# 12V_-5V_v_2.net
KiCad netlist of a schematic drawn in EAGLE
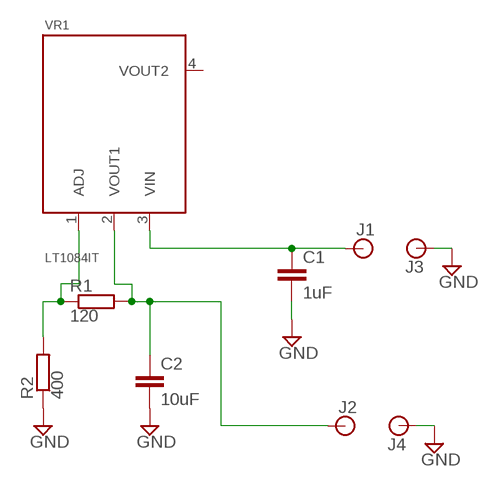
[diagram p0: schematic, sheet 1]

(export (version "E")
  (design (tool "Eeschema 10.0.6"))
  (components
    (comp (ref "C1")
      (value "1uF")
      (footprint "eagle-import:C0805")
      (libsource (lib "eagle-import") (part "C-EUC0805"))
    )
    (comp (ref "C2")
      (value "10uF")
      (footprint "eagle-import:C0805")
      (libsource (lib "eagle-import") (part "C-EUC0805"))
    )
    (comp (ref "J1")
      (value "BANANA_CONN")
      (footprint "eagle-import:BANANA_CONN")
      (libsource (lib "eagle-import") (part "BANANA_CONN"))
    )
    (comp (ref "J2")
      (value "BANANA_CONN")
      (footprint "eagle-import:BANANA_CONN")
      (libsource (lib "eagle-import") (part "BANANA_CONN"))
    )
    (comp (ref "J3")
      (value "BANANA_CONN")
      (footprint "eagle-import:BANANA_CONN")
      (libsource (lib "eagle-import") (part "BANANA_CONN"))
    )
    (comp (ref "J4")
      (value "BANANA_CONN")
      (footprint "eagle-import:BANANA_CONN")
      (libsource (lib "eagle-import") (part "BANANA_CONN"))
    )
    (comp (ref "R1")
      (value "120")
      (footprint "eagle-import:R0805")
      (libsource (lib "eagle-import") (part "R-EU_R0805"))
    )
    (comp (ref "R2")
      (value "400")
      (footprint "eagle-import:R0805")
      (libsource (lib "eagle-import") (part "R-EU_R0805"))
    )
    (comp (ref "VR1")
      (value "LT1084IT")
      (footprint "eagle-import:LT1084IT")
      (fields (field (name "MF") "Linear Technology"))
      (libsource (lib "eagle-import") (part "LT1084IT"))
    )
  )
  (nets
    (net (code "1") (name "GND") (class "Default")
      (node (ref "C1") (pin "2") (pinfunction "2_2") (pintype "passive"))
      (node (ref "C2") (pin "2") (pinfunction "2_2") (pintype "passive"))
      (node (ref "J3") (pin "P$1") (pinfunction "1_P$1") (pintype "passive"))
      (node (ref "J4") (pin "P$1") (pinfunction "1_P$1") (pintype "passive"))
      (node (ref "R2") (pin "1") (pinfunction "1_1") (pintype "passive"))
    )
    (net (code "2") (name "Net-(J1-1)") (class "Default")
      (node (ref "C1") (pin "1") (pinfunction "1_1") (pintype "passive"))
      (node (ref "J1") (pin "P$1") (pinfunction "1_P$1") (pintype "passive"))
      (node (ref "VR1") (pin "3") (pinfunction "VIN_3") (pintype "bidirectional"))
    )
    (net (code "3") (name "Net-(J2-1)") (class "Default")
      (node (ref "C2") (pin "1") (pinfunction "1_1") (pintype "passive"))
      (node (ref "J2") (pin "P$1") (pinfunction "1_P$1") (pintype "passive"))
      (node (ref "R1") (pin "2") (pinfunction "2_2") (pintype "passive"))
      (node (ref "VR1") (pin "2") (pinfunction "VOUT1_2") (pintype "bidirectional"))
    )
    (net (code "4") (name "Net-(VR1-ADJ)") (class "Default")
      (node (ref "R1") (pin "1") (pinfunction "1_1") (pintype "passive"))
      (node (ref "R2") (pin "2") (pinfunction "2_2") (pintype "passive"))
      (node (ref "VR1") (pin "1") (pinfunction "ADJ_1") (pintype "bidirectional"))
    )
    (net (code "5") (name "unconnected-(VR1-VOUT2-Pad4)") (class "Default")
      (node (ref "VR1") (pin "4") (pinfunction "VOUT2_4") (pintype "bidirectional"))
    )
  )
)
